# Sheet1_Updated_v4.net
KiCad netlist of a schematic drawn in Altium Designer
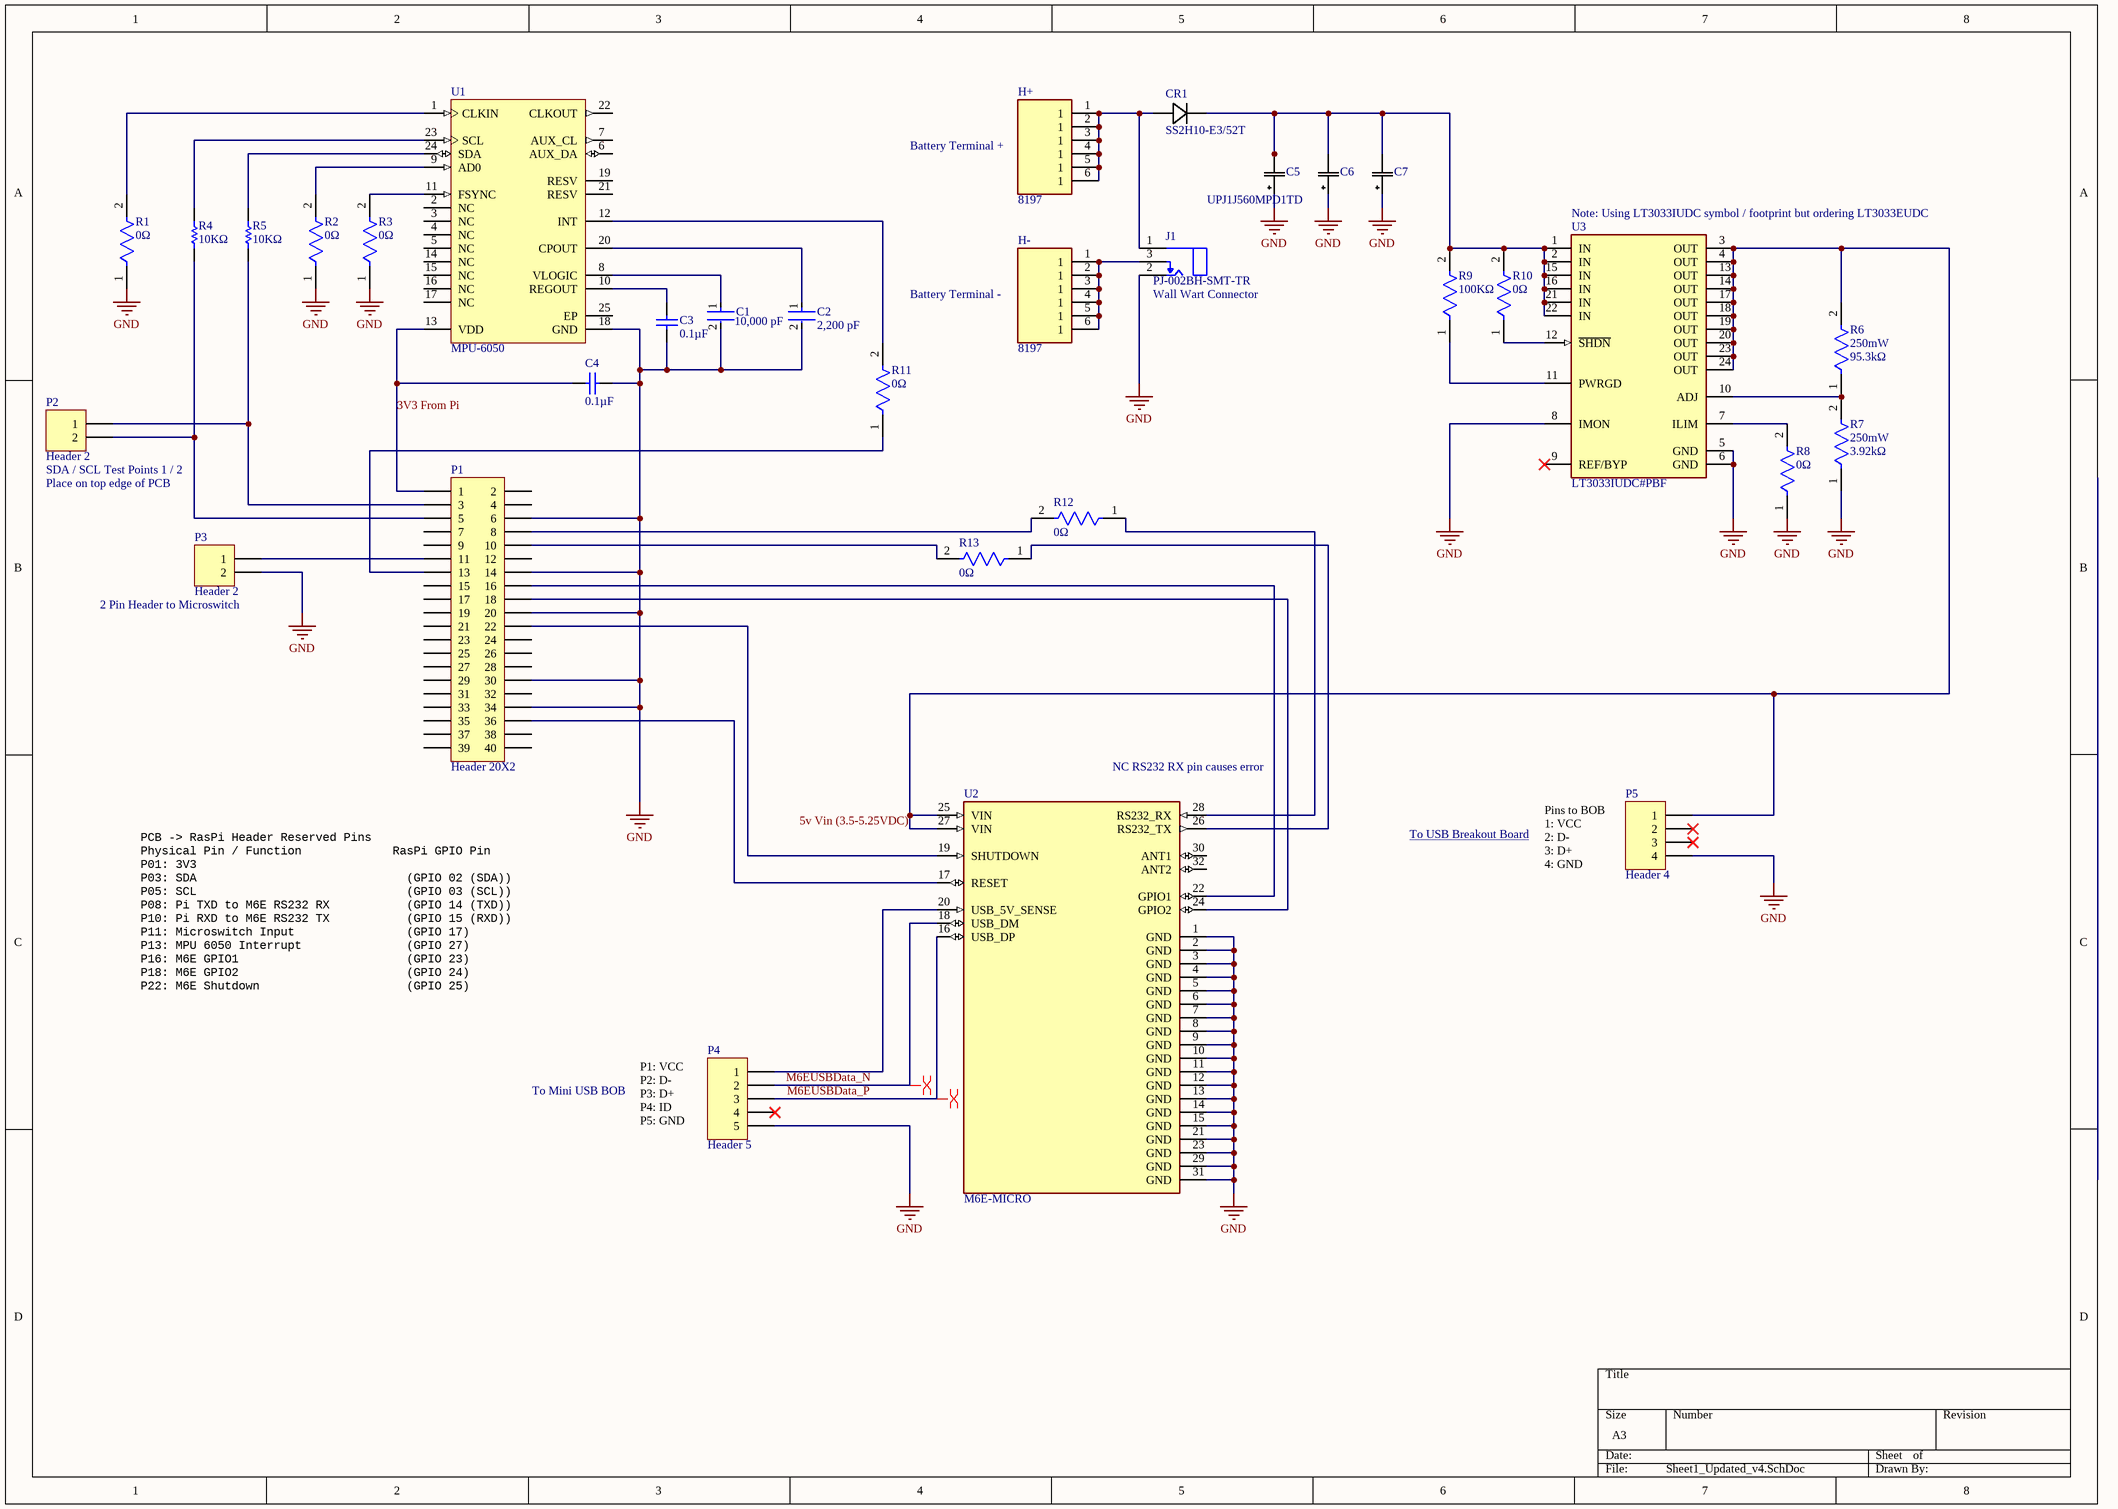
[diagram p0: Sheet1_Updated_v4.SchDoc]

(export (version "E")
  (design (tool "Eeschema 10.0.6"))
  (components
    (comp (ref "C1")
      (value "C1206C103K1RACTU")
      (footprint "FP-C1206C-EB-MFG")
      (description "Cap Ceramic 0.01uF 100V X7R 10% SMD 1206 125°C Plastic T/R")
      (fields
        (field (name "MANUFACTURER") "KEMET")
        (field (name "OCTOPART") "https://octopart.com/c1206c103k1ractu-kemet-117927")
        (field (name "CAPACITANCE") "10,000 pF")
      )
      (libsource (lib "Altium Content Vault") (part "b4654b650e69147ec39a6b967a45e02"))
    )
    (comp (ref "C2")
      (value "2,200 pF")
      (footprint "FP-C1206C-EB-MFG")
      (description "CAP CER 2200PF 50V X7R 1206")
      (fields
        (field (name "MANUFACTURER") "KEMET")
        (field (name "MANUFACTURER PART NUMBER") "C1206C222K5RACTU")
      )
      (libsource (lib "Altium Content Vault") (part "b4654b650e69147ec39a6b967a45e02"))
    )
    (comp (ref "C3")
      (value "C1206C104K5RACTU")
      (footprint "KEMT-1206-2_M")
      (description "CAP, Ceramic, 0.1 uF, +/- 10%, 50 V, -55 to 125 degC, 1206 (3216 Metric), RoHS, Tape and Reel")
      (fields (field (name "CAPACITANCE") "0.1µF") (field (name "MANUFACTURER") "Kemet"))
      (libsource (lib "Altium Content Vault") (part "CAP-NP-2"))
    )
    (comp (ref "C4")
      (value "C1206C104K5RACTU")
      (footprint "KEMT-1206-2_M")
      (description "CAP, Ceramic, 0.1 uF, +/- 10%, 50 V, -55 to 125 degC, 1206 (3216 Metric), RoHS, Tape and Reel")
      (fields (field (name "CAPACITANCE") "0.1µF") (field (name "MANUFACTURER") "Kemet"))
      (libsource (lib "Altium Content Vault") (part "CAP-NP-2"))
    )
    (comp (ref "C5")
      (value "UPJ1J560MPD1TD")
      (footprint "CAP_UPJ_8X15_NCH")
      (description "No Description Available")
      (fields (field (name "COPYRIGHT") "Copyright (C) 2018 Accelerated Designs. All rights reserved"))
      (libsource (lib "2021-02-17_22-04-36") (part "UPJ1J560MPD1TD"))
    )
    (comp (ref "C6")
      (value "UPJ1J560MPD1TD")
      (footprint "CAP_UPJ_8X15_NCH")
      (description "No Description Available")
      (fields (field (name "COPYRIGHT") "Copyright (C) 2018 Accelerated Designs. All rights reserved"))
      (libsource (lib "2021-02-17_22-04-36") (part "UPJ1J560MPD1TD"))
    )
    (comp (ref "C7")
      (value "UPJ1J560MPD1TD")
      (footprint "CAP_UPJ_8X15_NCH")
      (description "No Description Available")
      (fields (field (name "COPYRIGHT") "Copyright (C) 2018 Accelerated Designs. All rights reserved"))
      (libsource (lib "2021-02-17_22-04-36") (part "UPJ1J560MPD1TD"))
    )
    (comp (ref "CR1")
      (value "SS2H10-E3/52T")
      (footprint "DIODE_DO214AA")
      (description "No Description Available")
      (fields (field (name "COPYRIGHT") "Copyright (C) 2018 Accelerated Designs. All rights reserved"))
      (libsource (lib "2021-02-17_22-03-51") (part "SS2H10-E3/52T"))
    )
    (comp (ref "H+")
      (value "8197")
      (footprint "KEYSTONE_8197")
      (description "Magnet Neodymium Iron Boron _NdFeB_ 0.500 Dia x 0.750 H _12.7mm x 19.0mm_")
      (fields (field (name "MF") "Radial Magnet"))
      (libsource (lib "8197") (part "8197"))
    )
    (comp (ref "H-")
      (value "8197")
      (footprint "KEYSTONE_8197")
      (description "Magnet Neodymium Iron Boron _NdFeB_ 0.500 Dia x 0.750 H _12.7mm x 19.0mm_")
      (fields (field (name "MF") "Radial Magnet"))
      (libsource (lib "8197") (part "8197"))
    )
    (comp (ref "J1")
      (value "PJ-002BH-SMT-TR")
      (footprint "FP-PJ-002BH-SMT-TR-MFG")
      (description "CONN PWR JACK 2.5X5.5MM SOLDER")
      (fields
        (field (name "MANUFACTURER") "CUI Inc")
        (field (name "OCTOPART") "https://octopart.com/pj-002bh-smt-tr-cui-25947151")
      )
      (libsource (lib "Altium Content Vault") (part "020ff674638626da6de6501228ee46e"))
    )
    (comp (ref "P1")
      (value "Header 20X2")
      (footprint "HDR2X20")
      (description "Header, 20-Pin, Dual row")
      (fields (field (name "PUBLISHER") "Altium Limited"))
      (libsource (lib "Miscellaneous Connectors") (part "Header 20X2"))
    )
    (comp (ref "P2")
      (value "Header 2")
      (footprint "HDR1X2")
      (description "Header, 2-Pin")
      (fields (field (name "PUBLISHER") "Altium Limited"))
      (libsource (lib "Miscellaneous Connectors") (part "Header 2"))
    )
    (comp (ref "P3")
      (value "Header 2")
      (footprint "HDR1X2")
      (description "Header, 2-Pin")
      (fields (field (name "PUBLISHER") "Altium Limited"))
      (libsource (lib "Miscellaneous Connectors") (part "Header 2"))
    )
    (comp (ref "P4")
      (value "Header 5")
      (footprint "HDR1X5")
      (description "Header, 5-Pin")
      (fields (field (name "PUBLISHER") "Altium Limited"))
      (libsource (lib "Miscellaneous Connectors") (part "Header 5"))
    )
    (comp (ref "P5")
      (value "Header 4")
      (footprint "HDR1X4")
      (description "Header, 4-Pin")
      (fields (field (name "PUBLISHER") "Altium Limited"))
      (libsource (lib "Miscellaneous Connectors") (part "Header 4"))
    )
    (comp (ref "R1")
      (value "0Ω")
      (footprint "FP-RC1206-MFG")
      (description "RES SMD 0 OHM JUMPER 1/4W 1206")
      (fields
        (field (name "MANUFACTURER PART NUMBER") "RC1206JR-070RL")
        (field (name "MANUFACTURER") "YAGEO")
      )
      (libsource (lib "Altium Content Vault") (part "1029c3af85768c4190bb7ad29bc67b5"))
    )
    (comp (ref "R2")
      (value "0Ω")
      (footprint "FP-RC1206-MFG")
      (description "RES SMD 0 OHM JUMPER 1/4W 1206")
      (fields
        (field (name "MANUFACTURER PART NUMBER") "RC1206JR-070RL")
        (field (name "MANUFACTURER") "YAGEO")
      )
      (libsource (lib "Altium Content Vault") (part "1029c3af85768c4190bb7ad29bc67b5"))
    )
    (comp (ref "R3")
      (value "0Ω")
      (footprint "FP-RC1206-MFG")
      (description "RES SMD 0 OHM JUMPER 1/4W 1206")
      (fields
        (field (name "MANUFACTURER PART NUMBER") "RC1206JR-070RL")
        (field (name "MANUFACTURER") "YAGEO")
      )
      (libsource (lib "Altium Content Vault") (part "1029c3af85768c4190bb7ad29bc67b5"))
    )
    (comp (ref "R4")
      (value "RC1206FR-0710KL")
      (footprint "RESC3116X65X40ML10T20")
      (description "Chip Resistor, 10 KOhm, +/- 1%, 0.25 W, -55 to 155 degC, 1206 (3216 Metric), RoHS, Tape and Reel")
      (fields
        (field (name "TOLERANCE") "1%")
        (field (name "RESISTANCE") "10KΩ")
        (field (name "MANUFACTURER") "Yageo")
      )
      (libsource (lib "Altium Content Vault") (part "RES-2"))
    )
    (comp (ref "R5")
      (value "RC1206FR-0710KL")
      (footprint "RESC3116X65X40ML10T20")
      (description "Chip Resistor, 10 KOhm, +/- 1%, 0.25 W, -55 to 155 degC, 1206 (3216 Metric), RoHS, Tape and Reel")
      (fields
        (field (name "TOLERANCE") "1%")
        (field (name "RESISTANCE") "10KΩ")
        (field (name "MANUFACTURER") "Yageo")
      )
      (libsource (lib "Altium Content Vault") (part "RES-2"))
    )
    (comp (ref "R6")
      (value "CRCW120695K3FKEA")
      (footprint "FP-CRCW1206-e3-IPC_B")
      (description "RES Thick Film, 95.3kΩ, 1%, 0.25W, 100ppm/°C, 1206")
      (fields
        (field (name "TOLERANCE") "1%")
        (field (name "POWER RATING") "250mW")
        (field (name "RESISTANCE") "95.3kΩ")
      )
      (libsource (lib "Altium Content Vault") (part "1029c3af85768c4190bb7ad29bc67b5"))
    )
    (comp (ref "R7")
      (value "CRCW12063K92FKEA")
      (footprint "FP-CRCW1206-e3-IPC_C")
      (description "RES Thick Film, 3.92kΩ, 1%, 0.25W, 100ppm/°C, 1206")
      (fields
        (field (name "POWER RATING") "250mW")
        (field (name "RESISTANCE") "3.92kΩ")
        (field (name "TOLERANCE") "1%")
      )
      (libsource (lib "Altium Content Vault") (part "1029c3af85768c4190bb7ad29bc67b5"))
    )
    (comp (ref "R8")
      (value "0Ω")
      (footprint "FP-RC1206-MFG")
      (description "RES SMD 0 OHM JUMPER 1/4W 1206")
      (fields
        (field (name "MANUFACTURER PART NUMBER") "RC1206JR-070RL")
        (field (name "MANUFACTURER") "YAGEO")
      )
      (libsource (lib "Altium Content Vault") (part "1029c3af85768c4190bb7ad29bc67b5"))
    )
    (comp (ref "R9")
      (value "100KΩ")
      (footprint "FP-AC1206-MFG")
      (description "RES SMD 100K OHM 1% 1/4W 1206")
      (fields
        (field (name "OCTOPART") "https://octopart.com/ac1206fr-07100kl-yageo-21711116")
        (field (name "MANUFACTURER") "Yageo")
      )
      (libsource (lib "Altium Content Vault") (part "1029c3af85768c4190bb7ad29bc67b5"))
    )
    (comp (ref "R10")
      (value "0Ω")
      (footprint "FP-RC1206-MFG")
      (description "RES SMD 0 OHM JUMPER 1/4W 1206")
      (fields
        (field (name "MANUFACTURER PART NUMBER") "RC1206JR-070RL")
        (field (name "MANUFACTURER") "YAGEO")
      )
      (libsource (lib "Altium Content Vault") (part "1029c3af85768c4190bb7ad29bc67b5"))
    )
    (comp (ref "R11")
      (value "0Ω")
      (footprint "FP-RC1206-MFG")
      (description "RES SMD 0 OHM JUMPER 1/4W 1206")
      (fields
        (field (name "MANUFACTURER PART NUMBER") "RC1206JR-070RL")
        (field (name "MANUFACTURER") "YAGEO")
      )
      (libsource (lib "Altium Content Vault") (part "1029c3af85768c4190bb7ad29bc67b5"))
    )
    (comp (ref "R12")
      (value "0Ω")
      (footprint "FP-RC1206-MFG")
      (description "RES SMD 0 OHM JUMPER 1/4W 1206")
      (fields
        (field (name "MANUFACTURER PART NUMBER") "RC1206JR-070RL")
        (field (name "MANUFACTURER") "YAGEO")
      )
      (libsource (lib "Altium Content Vault") (part "1029c3af85768c4190bb7ad29bc67b5"))
    )
    (comp (ref "R13")
      (value "0Ω")
      (footprint "FP-RC1206-MFG")
      (description "RES SMD 0 OHM JUMPER 1/4W 1206")
      (fields
        (field (name "MANUFACTURER PART NUMBER") "RC1206JR-070RL")
        (field (name "MANUFACTURER") "YAGEO")
      )
      (libsource (lib "Altium Content Vault") (part "1029c3af85768c4190bb7ad29bc67b5"))
    )
    (comp (ref "U1")
      (value "MPU-6050")
      (footprint "IS-QFN-24_V")
      (fields (field (name "MANUFACTURER") "InvenSense"))
      (libsource (lib "Altium Content Vault") (part "IS-MPU-6050-QFN-24"))
    )
    (comp (ref "U2")
      (value "M6E-MICRO")
      (footprint "XCVR_M6E-MICRO")
      (description "KIT DEVELOPMENT M6E MICRO-LTE")
      (fields (field (name "MF") "ThingMagic, a"))
      (libsource (lib "M6E-MICRO") (part "M6E-MICRO"))
    )
    (comp (ref "U3")
      (value "LT3033IUDC#PBF")
      (footprint "FP-UDC-20-05-08-1536-MFG")
      (description "IC REG LINEAR POS ADJ 3A 20QFN")
      (fields
        (field (name "MANUFACTURER") "Analog Devices")
        (field (name "OCTOPART") "https://octopart.com/lt3033iudc%23pbf-analog+devices-95403585")
      )
      (libsource (lib "Altium Content Vault") (part "32fad297b9cb76d0c6b2a9524b0e8e6"))
    )
  )
  (nets
    (net (code "1") (name "/3V3 From Pi") (class "Default")
      (node (ref "C4") (pin "2") (pinfunction "2_2") (pintype "passive"))
      (node (ref "P1") (pin "1") (pinfunction "1_1") (pintype "passive"))
      (node (ref "U1") (pin "13") (pinfunction "VDD_13") (pintype "power_in"))
    )
    (net (code "2") (name "/5v Vin (3.5-5.25VDC)") (class "Default")
      (node (ref "P5") (pin "1") (pinfunction "1_1") (pintype "passive"))
      (node (ref "R6") (pin "2") (pinfunction "2_2") (pintype "passive"))
      (node (ref "U2") (pin "25") (pinfunction "VIN_25") (pintype "input"))
      (node (ref "U2") (pin "27") (pinfunction "VIN_27") (pintype "input"))
      (node (ref "U3") (pin "13") (pinfunction "OUT_13") (pintype "power_in"))
      (node (ref "U3") (pin "14") (pinfunction "OUT_14") (pintype "power_in"))
      (node (ref "U3") (pin "17") (pinfunction "OUT_17") (pintype "power_in"))
      (node (ref "U3") (pin "18") (pinfunction "OUT_18") (pintype "power_in"))
      (node (ref "U3") (pin "19") (pinfunction "OUT_19") (pintype "power_in"))
      (node (ref "U3") (pin "20") (pinfunction "OUT_20") (pintype "power_in"))
      (node (ref "U3") (pin "23") (pinfunction "OUT_23") (pintype "power_in"))
      (node (ref "U3") (pin "24") (pinfunction "OUT_24") (pintype "power_in"))
      (node (ref "U3") (pin "3") (pinfunction "OUT_3") (pintype "power_in"))
      (node (ref "U3") (pin "4") (pinfunction "OUT_4") (pintype "power_in"))
    )
    (net (code "3") (name "/M6EUSBData_N") (class "Default")
      (node (ref "P4") (pin "2") (pinfunction "2_2") (pintype "passive"))
      (node (ref "U2") (pin "18") (pinfunction "USB_DM_18") (pintype "bidirectional"))
    )
    (net (code "4") (name "/M6EUSBData_P") (class "Default")
      (node (ref "P4") (pin "3") (pinfunction "3_3") (pintype "passive"))
      (node (ref "U2") (pin "16") (pinfunction "USB_DP_16") (pintype "bidirectional"))
    )
    (net (code "5") (name "GND") (class "Default")
      (node (ref "C1") (pin "2") (pinfunction "2_2") (pintype "passive"))
      (node (ref "C2") (pin "2") (pinfunction "2_2") (pintype "passive"))
      (node (ref "C3") (pin "1") (pinfunction "1_1") (pintype "passive"))
      (node (ref "C4") (pin "1") (pinfunction "1_1") (pintype "passive"))
      (node (ref "C5") (pin "1") (pinfunction "1_1") (pintype "passive"))
      (node (ref "C6") (pin "1") (pinfunction "1_1") (pintype "passive"))
      (node (ref "C7") (pin "1") (pinfunction "1_1") (pintype "passive"))
      (node (ref "J1") (pin "2") (pinfunction "2_2") (pintype "passive"))
      (node (ref "P1") (pin "14") (pinfunction "14_14") (pintype "passive"))
      (node (ref "P1") (pin "20") (pinfunction "20_20") (pintype "passive"))
      (node (ref "P1") (pin "30") (pinfunction "30_30") (pintype "passive"))
      (node (ref "P1") (pin "34") (pinfunction "34_34") (pintype "passive"))
      (node (ref "P1") (pin "6") (pinfunction "6_6") (pintype "passive"))
      (node (ref "P3") (pin "2") (pinfunction "2_2") (pintype "passive"))
      (node (ref "P4") (pin "5") (pinfunction "5_5") (pintype "passive"))
      (node (ref "P5") (pin "4") (pinfunction "4_4") (pintype "passive"))
      (node (ref "R1") (pin "1") (pinfunction "1_1") (pintype "passive"))
      (node (ref "R2") (pin "1") (pinfunction "1_1") (pintype "passive"))
      (node (ref "R3") (pin "1") (pinfunction "1_1") (pintype "passive"))
      (node (ref "R7") (pin "1") (pinfunction "1_1") (pintype "passive"))
      (node (ref "R8") (pin "1") (pinfunction "1_1") (pintype "passive"))
      (node (ref "U1") (pin "18") (pinfunction "GND_18") (pintype "power_in"))
      (node (ref "U2") (pin "1") (pinfunction "GND_1") (pintype "power_in"))
      (node (ref "U2") (pin "10") (pinfunction "GND_10") (pintype "power_in"))
      (node (ref "U2") (pin "11") (pinfunction "GND_11") (pintype "power_in"))
      (node (ref "U2") (pin "12") (pinfunction "GND_12") (pintype "power_in"))
      (node (ref "U2") (pin "13") (pinfunction "GND_13") (pintype "power_in"))
      (node (ref "U2") (pin "14") (pinfunction "GND_14") (pintype "power_in"))
      (node (ref "U2") (pin "15") (pinfunction "GND_15") (pintype "power_in"))
      (node (ref "U2") (pin "2") (pinfunction "GND_2") (pintype "power_in"))
      (node (ref "U2") (pin "21") (pinfunction "GND_21") (pintype "power_in"))
      (node (ref "U2") (pin "23") (pinfunction "GND_23") (pintype "power_in"))
      (node (ref "U2") (pin "29") (pinfunction "GND_29") (pintype "power_in"))
      (node (ref "U2") (pin "3") (pinfunction "GND_3") (pintype "power_in"))
      (node (ref "U2") (pin "31") (pinfunction "GND_31") (pintype "power_in"))
      (node (ref "U2") (pin "4") (pinfunction "GND_4") (pintype "power_in"))
      (node (ref "U2") (pin "5") (pinfunction "GND_5") (pintype "power_in"))
      (node (ref "U2") (pin "6") (pinfunction "GND_6") (pintype "power_in"))
      (node (ref "U2") (pin "7") (pinfunction "GND_7") (pintype "power_in"))
      (node (ref "U2") (pin "8") (pinfunction "GND_8") (pintype "power_in"))
      (node (ref "U2") (pin "9") (pinfunction "GND_9") (pintype "power_in"))
      (node (ref "U3") (pin "5") (pinfunction "GND_5") (pintype "power_in"))
      (node (ref "U3") (pin "6") (pinfunction "GND_6") (pintype "power_in"))
      (node (ref "U3") (pin "8") (pinfunction "IMON_8") (pintype "passive"))
    )
    (net (code "6") (name "Net-(C5-Pad2)") (class "Default")
      (node (ref "C5") (pin "2") (pinfunction "2_2") (pintype "passive"))
      (node (ref "C6") (pin "2") (pinfunction "2_2") (pintype "passive"))
      (node (ref "C7") (pin "2") (pinfunction "2_2") (pintype "passive"))
      (node (ref "CR1") (pin "1") (pinfunction "1_1") (pintype "passive"))
      (node (ref "R10") (pin "2") (pinfunction "2_2") (pintype "passive"))
      (node (ref "R9") (pin "2") (pinfunction "2_2") (pintype "passive"))
      (node (ref "U3") (pin "1") (pinfunction "IN_1") (pintype "power_in"))
      (node (ref "U3") (pin "15") (pinfunction "IN_15") (pintype "power_in"))
      (node (ref "U3") (pin "16") (pinfunction "IN_16") (pintype "power_in"))
      (node (ref "U3") (pin "2") (pinfunction "IN_2") (pintype "power_in"))
      (node (ref "U3") (pin "21") (pinfunction "IN_21") (pintype "power_in"))
      (node (ref "U3") (pin "22") (pinfunction "IN_22") (pintype "power_in"))
    )
    (net (code "7") (name "Net-(CR1-Pad2)") (class "Default")
      (node (ref "CR1") (pin "2") (pinfunction "2_2") (pintype "passive"))
      (node (ref "H+") (pin "1") (pinfunction "1_1") (pintype "passive"))
      (node (ref "H+") (pin "2") (pinfunction "1_2") (pintype "passive"))
      (node (ref "H+") (pin "3") (pinfunction "1_3") (pintype "passive"))
      (node (ref "H+") (pin "4") (pinfunction "1_4") (pintype "passive"))
      (node (ref "H+") (pin "5") (pinfunction "1_5") (pintype "passive"))
      (node (ref "H+") (pin "6") (pinfunction "1_6") (pintype "passive"))
      (node (ref "J1") (pin "1") (pinfunction "1_1") (pintype "passive"))
    )
    (net (code "8") (name "Net-(H--1-Pad2)") (class "Default")
      (node (ref "H-") (pin "1") (pinfunction "1_1") (pintype "passive"))
      (node (ref "H-") (pin "2") (pinfunction "1_2") (pintype "passive"))
      (node (ref "H-") (pin "3") (pinfunction "1_3") (pintype "passive"))
      (node (ref "H-") (pin "4") (pinfunction "1_4") (pintype "passive"))
      (node (ref "H-") (pin "5") (pinfunction "1_5") (pintype "passive"))
      (node (ref "H-") (pin "6") (pinfunction "1_6") (pintype "passive"))
      (node (ref "J1") (pin "3") (pinfunction "3_3") (pintype "passive"))
    )
    (net (code "9") (name "Net-(P1-Pad3)") (class "Default")
      (node (ref "P1") (pin "3") (pinfunction "3_3") (pintype "passive"))
      (node (ref "P2") (pin "1") (pinfunction "1_1") (pintype "passive"))
      (node (ref "R5") (pin "1") (pinfunction "1_1") (pintype "passive"))
    )
    (net (code "10") (name "Net-(P1-Pad5)") (class "Default")
      (node (ref "P1") (pin "5") (pinfunction "5_5") (pintype "passive"))
      (node (ref "P2") (pin "2") (pinfunction "2_2") (pintype "passive"))
      (node (ref "R4") (pin "1") (pinfunction "1_1") (pintype "passive"))
    )
    (net (code "11") (name "Net-(P1-Pad8)") (class "Default")
      (node (ref "P1") (pin "8") (pinfunction "8_8") (pintype "passive"))
      (node (ref "R12") (pin "2") (pinfunction "2_2") (pintype "passive"))
    )
    (net (code "12") (name "Net-(P1-Pad10)") (class "Default")
      (node (ref "P1") (pin "10") (pinfunction "10_10") (pintype "passive"))
      (node (ref "R13") (pin "2") (pinfunction "2_2") (pintype "passive"))
    )
    (net (code "13") (name "Net-(P1-Pad11)") (class "Default")
      (node (ref "P1") (pin "11") (pinfunction "11_11") (pintype "passive"))
      (node (ref "P3") (pin "1") (pinfunction "1_1") (pintype "passive"))
    )
    (net (code "14") (name "Net-(P1-Pad13)") (class "Default")
      (node (ref "P1") (pin "13") (pinfunction "13_13") (pintype "passive"))
      (node (ref "R11") (pin "1") (pinfunction "1_1") (pintype "passive"))
    )
    (net (code "15") (name "Net-(U1-AD0)") (class "Default")
      (node (ref "R2") (pin "2") (pinfunction "2_2") (pintype "passive"))
      (node (ref "U1") (pin "9") (pinfunction "AD0_9") (pintype "input"))
    )
    (net (code "16") (name "Net-(U1-CLKIN)") (class "Default")
      (node (ref "R1") (pin "2") (pinfunction "2_2") (pintype "passive"))
      (node (ref "U1") (pin "1") (pinfunction "CLKIN_1") (pintype "input"))
    )
    (net (code "17") (name "Net-(U1-CPOUT)") (class "Default")
      (node (ref "C2") (pin "1") (pinfunction "1_1") (pintype "passive"))
      (node (ref "U1") (pin "20") (pinfunction "CPOUT_20") (pintype "passive"))
    )
    (net (code "18") (name "Net-(U1-FSYNC)") (class "Default")
      (node (ref "R3") (pin "2") (pinfunction "2_2") (pintype "passive"))
      (node (ref "U1") (pin "11") (pinfunction "FSYNC_11") (pintype "input"))
    )
    (net (code "19") (name "Net-(U1-INT)") (class "Default")
      (node (ref "R11") (pin "2") (pinfunction "2_2") (pintype "passive"))
      (node (ref "U1") (pin "12") (pinfunction "INT_12") (pintype "open_collector"))
    )
    (net (code "20") (name "Net-(U1-REGOUT)") (class "Default")
      (node (ref "C3") (pin "2") (pinfunction "2_2") (pintype "passive"))
      (node (ref "U1") (pin "10") (pinfunction "REGOUT_10") (pintype "passive"))
    )
    (net (code "21") (name "Net-(U1-SCL)") (class "Default")
      (node (ref "R4") (pin "2") (pinfunction "2_2") (pintype "passive"))
      (node (ref "U1") (pin "23") (pinfunction "SCL_23") (pintype "input"))
    )
    (net (code "22") (name "Net-(U1-SDA)") (class "Default")
      (node (ref "R5") (pin "2") (pinfunction "2_2") (pintype "passive"))
      (node (ref "U1") (pin "24") (pinfunction "SDA_24") (pintype "bidirectional"))
    )
    (net (code "23") (name "Net-(U1-VLOGIC)") (class "Default")
      (node (ref "C1") (pin "1") (pinfunction "1_1") (pintype "passive"))
      (node (ref "U1") (pin "8") (pinfunction "VLOGIC_8") (pintype "power_in"))
    )
    (net (code "24") (name "Net-(U2-GPIO1)") (class "Default")
      (node (ref "P1") (pin "16") (pinfunction "16_16") (pintype "passive"))
      (node (ref "U2") (pin "22") (pinfunction "GPIO1_22") (pintype "bidirectional"))
    )
    (net (code "25") (name "Net-(U2-GPIO2)") (class "Default")
      (node (ref "P1") (pin "18") (pinfunction "18_18") (pintype "passive"))
      (node (ref "U2") (pin "24") (pinfunction "GPIO2_24") (pintype "bidirectional"))
    )
    (net (code "26") (name "Net-(U2-RESET)") (class "Default")
      (node (ref "P1") (pin "36") (pinfunction "36_36") (pintype "passive"))
      (node (ref "U2") (pin "17") (pinfunction "RESET_17") (pintype "bidirectional"))
    )
    (net (code "27") (name "Net-(U2-RS232_RX)") (class "Default")
      (node (ref "R12") (pin "1") (pinfunction "1_1") (pintype "passive"))
      (node (ref "U2") (pin "28") (pinfunction "RS232_RX_28") (pintype "input"))
    )
    (net (code "28") (name "Net-(U2-RS232_TX)") (class "Default")
      (node (ref "R13") (pin "1") (pinfunction "1_1") (pintype "passive"))
      (node (ref "U2") (pin "26") (pinfunction "RS232_TX_26") (pintype "output"))
    )
    (net (code "29") (name "Net-(U2-SHUTDOWN)") (class "Default")
      (node (ref "P1") (pin "22") (pinfunction "22_22") (pintype "passive"))
      (node (ref "U2") (pin "19") (pinfunction "SHUTDOWN_19") (pintype "input"))
    )
    (net (code "30") (name "Net-(U2-USB_5V_SENSE)") (class "Default")
      (node (ref "P4") (pin "1") (pinfunction "1_1") (pintype "passive"))
      (node (ref "U2") (pin "20") (pinfunction "USB_5V_SENSE_20") (pintype "input"))
    )
    (net (code "31") (name "Net-(U3-ADJ)") (class "Default")
      (node (ref "R6") (pin "1") (pinfunction "1_1") (pintype "passive"))
      (node (ref "R7") (pin "2") (pinfunction "2_2") (pintype "passive"))
      (node (ref "U3") (pin "10") (pinfunction "ADJ_10") (pintype "passive"))
    )
    (net (code "32") (name "Net-(U3-ILIM)") (class "Default")
      (node (ref "R8") (pin "2") (pinfunction "2_2") (pintype "passive"))
      (node (ref "U3") (pin "7") (pinfunction "ILIM_7") (pintype "passive"))
    )
    (net (code "33") (name "Net-(U3-PWRGD)") (class "Default")
      (node (ref "R9") (pin "1") (pinfunction "1_1") (pintype "passive"))
      (node (ref "U3") (pin "11") (pinfunction "PWRGD_11") (pintype "open_collector"))
    )
    (net (code "34") (name "Net-(U3-~{SHDN})") (class "Default")
      (node (ref "R10") (pin "1") (pinfunction "1_1") (pintype "passive"))
      (node (ref "U3") (pin "12") (pinfunction "~{SHDN}_12") (pintype "input"))
    )
    (net (code "35") (name "unconnected-(P1-Pad2)") (class "Default")
      (node (ref "P1") (pin "2") (pinfunction "2_2") (pintype "passive"))
    )
    (net (code "36") (name "unconnected-(P1-Pad4)") (class "Default")
      (node (ref "P1") (pin "4") (pinfunction "4_4") (pintype "passive"))
    )
    (net (code "37") (name "unconnected-(P1-Pad7)") (class "Default")
      (node (ref "P1") (pin "7") (pinfunction "7_7") (pintype "passive"))
    )
    (net (code "38") (name "unconnected-(P1-Pad9)") (class "Default")
      (node (ref "P1") (pin "9") (pinfunction "9_9") (pintype "passive"))
    )
    (net (code "39") (name "unconnected-(P1-Pad12)") (class "Default")
      (node (ref "P1") (pin "12") (pinfunction "12_12") (pintype "passive"))
    )
    (net (code "40") (name "unconnected-(P1-Pad15)") (class "Default")
      (node (ref "P1") (pin "15") (pinfunction "15_15") (pintype "passive"))
    )
    (net (code "41") (name "unconnected-(P1-Pad17)") (class "Default")
      (node (ref "P1") (pin "17") (pinfunction "17_17") (pintype "passive"))
    )
    (net (code "42") (name "unconnected-(P1-Pad19)") (class "Default")
      (node (ref "P1") (pin "19") (pinfunction "19_19") (pintype "passive"))
    )
    (net (code "43") (name "unconnected-(P1-Pad21)") (class "Default")
      (node (ref "P1") (pin "21") (pinfunction "21_21") (pintype "passive"))
    )
    (net (code "44") (name "unconnected-(P1-Pad23)") (class "Default")
      (node (ref "P1") (pin "23") (pinfunction "23_23") (pintype "passive"))
    )
    (net (code "45") (name "unconnected-(P1-Pad24)") (class "Default")
      (node (ref "P1") (pin "24") (pinfunction "24_24") (pintype "passive"))
    )
    (net (code "46") (name "unconnected-(P1-Pad25)") (class "Default")
      (node (ref "P1") (pin "25") (pinfunction "25_25") (pintype "passive"))
    )
    (net (code "47") (name "unconnected-(P1-Pad26)") (class "Default")
      (node (ref "P1") (pin "26") (pinfunction "26_26") (pintype "passive"))
    )
    (net (code "48") (name "unconnected-(P1-Pad27)") (class "Default")
      (node (ref "P1") (pin "27") (pinfunction "27_27") (pintype "passive"))
    )
    (net (code "49") (name "unconnected-(P1-Pad28)") (class "Default")
      (node (ref "P1") (pin "28") (pinfunction "28_28") (pintype "passive"))
    )
    (net (code "50") (name "unconnected-(P1-Pad29)") (class "Default")
      (node (ref "P1") (pin "29") (pinfunction "29_29") (pintype "passive"))
    )
    (net (code "51") (name "unconnected-(P1-Pad31)") (class "Default")
      (node (ref "P1") (pin "31") (pinfunction "31_31") (pintype "passive"))
    )
    (net (code "52") (name "unconnected-(P1-Pad32)") (class "Default")
      (node (ref "P1") (pin "32") (pinfunction "32_32") (pintype "passive"))
    )
    (net (code "53") (name "unconnected-(P1-Pad33)") (class "Default")
      (node (ref "P1") (pin "33") (pinfunction "33_33") (pintype "passive"))
    )
    (net (code "54") (name "unconnected-(P1-Pad35)") (class "Default")
      (node (ref "P1") (pin "35") (pinfunction "35_35") (pintype "passive"))
    )
    (net (code "55") (name "unconnected-(P1-Pad37)") (class "Default")
      (node (ref "P1") (pin "37") (pinfunction "37_37") (pintype "passive"))
    )
    (net (code "56") (name "unconnected-(P1-Pad38)") (class "Default")
      (node (ref "P1") (pin "38") (pinfunction "38_38") (pintype "passive"))
    )
    (net (code "57") (name "unconnected-(P1-Pad39)") (class "Default")
      (node (ref "P1") (pin "39") (pinfunction "39_39") (pintype "passive"))
    )
    (net (code "58") (name "unconnected-(P1-Pad40)") (class "Default")
      (node (ref "P1") (pin "40") (pinfunction "40_40") (pintype "passive"))
    )
    (net (code "59") (name "unconnected-(P4-Pad4)") (class "Default")
      (node (ref "P4") (pin "4") (pinfunction "4_4") (pintype "passive+no_connect"))
    )
    (net (code "60") (name "unconnected-(P5-Pad2)") (class "Default")
      (node (ref "P5") (pin "2") (pinfunction "2_2") (pintype "passive+no_connect"))
    )
    (net (code "61") (name "unconnected-(P5-Pad3)") (class "Default")
      (node (ref "P5") (pin "3") (pinfunction "3_3") (pintype "passive+no_connect"))
    )
    (net (code "62") (name "unconnected-(U1-AUX_CL-Pad7)") (class "Default")
      (node (ref "U1") (pin "7") (pinfunction "AUX_CL_7") (pintype "output"))
    )
    (net (code "63") (name "unconnected-(U1-AUX_DA-Pad6)") (class "Default")
      (node (ref "U1") (pin "6") (pinfunction "AUX_DA_6") (pintype "bidirectional"))
    )
    (net (code "64") (name "unconnected-(U1-CLKOUT-Pad22)") (class "Default")
      (node (ref "U1") (pin "22") (pinfunction "CLKOUT_22") (pintype "output"))
    )
    (net (code "65") (name "unconnected-(U1-EP-Pad25)") (class "Default")
      (node (ref "U1") (pin "25") (pinfunction "EP_25") (pintype "power_in"))
    )
    (net (code "66") (name "unconnected-(U1-NC-Pad2)") (class "Default")
      (node (ref "U1") (pin "2") (pinfunction "NC_2") (pintype "passive"))
    )
    (net (code "67") (name "unconnected-(U1-NC-Pad3)") (class "Default")
      (node (ref "U1") (pin "3") (pinfunction "NC_3") (pintype "passive"))
    )
    (net (code "68") (name "unconnected-(U1-NC-Pad4)") (class "Default")
      (node (ref "U1") (pin "4") (pinfunction "NC_4") (pintype "passive"))
    )
    (net (code "69") (name "unconnected-(U1-NC-Pad5)") (class "Default")
      (node (ref "U1") (pin "5") (pinfunction "NC_5") (pintype "passive"))
    )
    (net (code "70") (name "unconnected-(U1-NC-Pad14)") (class "Default")
      (node (ref "U1") (pin "14") (pinfunction "NC_14") (pintype "passive"))
    )
    (net (code "71") (name "unconnected-(U1-NC-Pad15)") (class "Default")
      (node (ref "U1") (pin "15") (pinfunction "NC_15") (pintype "passive"))
    )
    (net (code "72") (name "unconnected-(U1-NC-Pad16)") (class "Default")
      (node (ref "U1") (pin "16") (pinfunction "NC_16") (pintype "passive"))
    )
    (net (code "73") (name "unconnected-(U1-NC-Pad17)") (class "Default")
      (node (ref "U1") (pin "17") (pinfunction "NC_17") (pintype "passive"))
    )
    (net (code "74") (name "unconnected-(U1-RESV-Pad19)") (class "Default")
      (node (ref "U1") (pin "19") (pinfunction "RESV_19") (pintype "passive"))
    )
    (net (code "75") (name "unconnected-(U1-RESV-Pad21)") (class "Default")
      (node (ref "U1") (pin "21") (pinfunction "RESV_21") (pintype "passive"))
    )
    (net (code "76") (name "unconnected-(U2-ANT1-Pad30)") (class "Default")
      (node (ref "U2") (pin "30") (pinfunction "ANT1_30") (pintype "bidirectional"))
    )
    (net (code "77") (name "unconnected-(U2-ANT2-Pad32)") (class "Default")
      (node (ref "U2") (pin "32") (pinfunction "ANT2_32") (pintype "bidirectional"))
    )
    (net (code "78") (name "unconnected-(U3-REF{slash}BYP-Pad9)") (class "Default")
      (node (ref "U3") (pin "9") (pinfunction "REF/BYP_9") (pintype "passive+no_connect"))
    )
  )
)
